# Orders.net
KiCad netlist of a schematic drawn in EAGLE
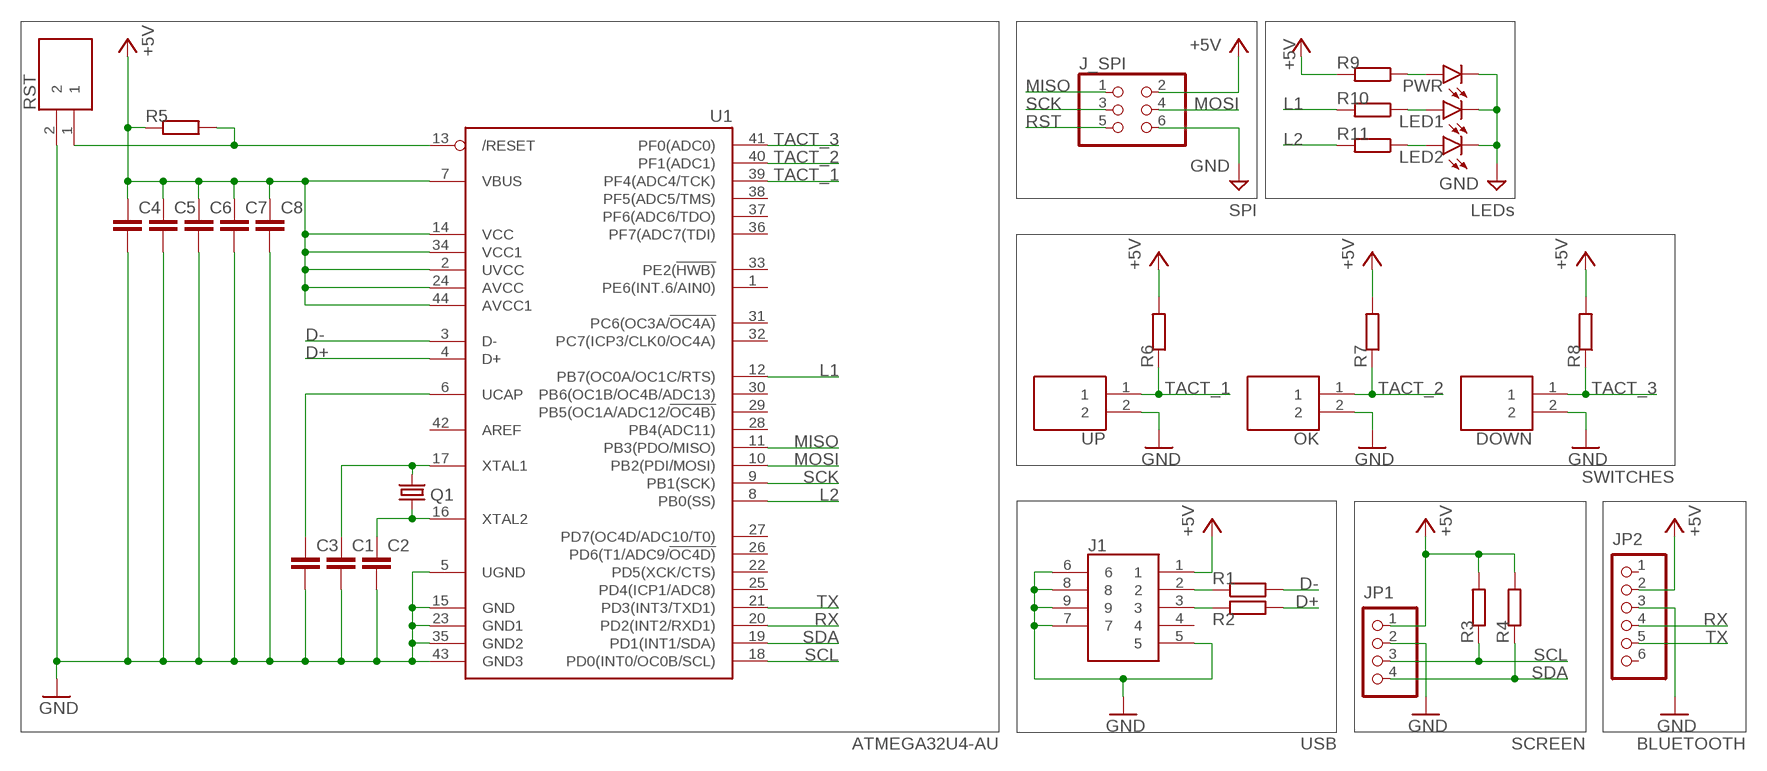
[diagram p0: schematic, sheet 1]

(export (version "E")
  (design (tool "Eeschema 10.0.6"))
  (components
    (comp (ref "C1")
      (value "C-EUC1206")
      (footprint "eagle-import:C1206")
      (libsource (lib "eagle-import") (part "C-EUC1206"))
    )
    (comp (ref "C2")
      (value "C-EUC1206")
      (footprint "eagle-import:C1206")
      (libsource (lib "eagle-import") (part "C-EUC1206"))
    )
    (comp (ref "C3")
      (value "C-EUC1206")
      (footprint "eagle-import:C1206")
      (libsource (lib "eagle-import") (part "C-EUC1206"))
    )
    (comp (ref "C4")
      (value "C-EUC1206")
      (footprint "eagle-import:C1206")
      (libsource (lib "eagle-import") (part "C-EUC1206"))
    )
    (comp (ref "C5")
      (value "C-EUC1206")
      (footprint "eagle-import:C1206")
      (libsource (lib "eagle-import") (part "C-EUC1206"))
    )
    (comp (ref "C6")
      (value "C-EUC1206")
      (footprint "eagle-import:C1206")
      (libsource (lib "eagle-import") (part "C-EUC1206"))
    )
    (comp (ref "C7")
      (value "C-EUC1206")
      (footprint "eagle-import:C1206")
      (libsource (lib "eagle-import") (part "C-EUC1206"))
    )
    (comp (ref "C8")
      (value "C-EUC1206")
      (footprint "eagle-import:C1206")
      (libsource (lib "eagle-import") (part "C-EUC1206"))
    )
    (comp (ref "DOWN")
      (value "KSR231GLFS")
      (footprint "eagle-import:KSR")
      (fields (field (name "MOUSER_PART_NUMBER") "611-KSR231GLFS") (field (name "RS_PART_NUMBER") "7931673P"))
      (libsource (lib "eagle-import") (part "KSR231GLFS"))
    )
    (comp (ref "J1")
      (value "10104111-0001LF")
      (footprint "eagle-import:101041110001LF")
      (fields
        (field (name "MOUSER_PART_NUMBER") "649-10104111-0001LF")
        (field (name "RS_PART_NUMBER") "7142353")
      )
      (libsource (lib "eagle-import") (part "10104111-0001LF"))
    )
    (comp (ref "JP1")
      (value "PINHD-1X4")
      (footprint "eagle-import:1X04")
      (libsource (lib "eagle-import") (part "PINHD-1X4"))
    )
    (comp (ref "JP2")
      (value "PINHD-1X6")
      (footprint "eagle-import:1X06")
      (libsource (lib "eagle-import") (part "PINHD-1X6"))
    )
    (comp (ref "J_SPI")
      (value "PINHD-2X3")
      (footprint "eagle-import:2X03")
      (libsource (lib "eagle-import") (part "PINHD-2X3"))
    )
    (comp (ref "LED1")
      (value "LED3MM")
      (footprint "eagle-import:LED3MM")
      (libsource (lib "eagle-import") (part "LED3MM"))
    )
    (comp (ref "LED2")
      (value "LED3MM")
      (footprint "eagle-import:LED3MM")
      (libsource (lib "eagle-import") (part "LED3MM"))
    )
    (comp (ref "OK")
      (value "KSR231GLFS")
      (footprint "eagle-import:KSR")
      (fields (field (name "MOUSER_PART_NUMBER") "611-KSR231GLFS") (field (name "RS_PART_NUMBER") "7931673P"))
      (libsource (lib "eagle-import") (part "KSR231GLFS"))
    )
    (comp (ref "PWR")
      (value "LED3MM")
      (footprint "eagle-import:LED3MM")
      (libsource (lib "eagle-import") (part "LED3MM"))
    )
    (comp (ref "Q1")
      (value "CRYSTALHC49UP")
      (footprint "eagle-import:HC49UP")
      (libsource (lib "eagle-import") (part "CRYSTALHC49UP"))
    )
    (comp (ref "R1")
      (value "R-EU_R1206")
      (footprint "eagle-import:R1206")
      (libsource (lib "eagle-import") (part "R-EU_R1206"))
    )
    (comp (ref "R2")
      (value "R-EU_R1206")
      (footprint "eagle-import:R1206")
      (libsource (lib "eagle-import") (part "R-EU_R1206"))
    )
    (comp (ref "R3")
      (value "R-EU_R1206")
      (footprint "eagle-import:R1206")
      (libsource (lib "eagle-import") (part "R-EU_R1206"))
    )
    (comp (ref "R4")
      (value "R-EU_R1206")
      (footprint "eagle-import:R1206")
      (libsource (lib "eagle-import") (part "R-EU_R1206"))
    )
    (comp (ref "R5")
      (value "R-EU_R1206")
      (footprint "eagle-import:R1206")
      (libsource (lib "eagle-import") (part "R-EU_R1206"))
    )
    (comp (ref "R6")
      (value "R-EU_R1206")
      (footprint "eagle-import:R1206")
      (libsource (lib "eagle-import") (part "R-EU_R1206"))
    )
    (comp (ref "R7")
      (value "R-EU_R1206")
      (footprint "eagle-import:R1206")
      (libsource (lib "eagle-import") (part "R-EU_R1206"))
    )
    (comp (ref "R8")
      (value "R-EU_R1206")
      (footprint "eagle-import:R1206")
      (libsource (lib "eagle-import") (part "R-EU_R1206"))
    )
    (comp (ref "R9")
      (value "R-EU_R1206")
      (footprint "eagle-import:R1206")
      (libsource (lib "eagle-import") (part "R-EU_R1206"))
    )
    (comp (ref "R10")
      (value "R-EU_R1206")
      (footprint "eagle-import:R1206")
      (libsource (lib "eagle-import") (part "R-EU_R1206"))
    )
    (comp (ref "R11")
      (value "R-EU_R1206")
      (footprint "eagle-import:R1206")
      (libsource (lib "eagle-import") (part "R-EU_R1206"))
    )
    (comp (ref "RST")
      (value "KSR231GLFS")
      (footprint "eagle-import:KSR")
      (fields (field (name "MOUSER_PART_NUMBER") "611-KSR231GLFS") (field (name "RS_PART_NUMBER") "7931673P"))
      (libsource (lib "eagle-import") (part "KSR231GLFS"))
    )
    (comp (ref "U1")
      (value "ATMEGA32U4-AU")
      (footprint "eagle-import:TQFP44")
      (libsource (lib "eagle-import") (part "ATMEGA32U4-AU"))
    )
    (comp (ref "UP")
      (value "KSR231GLFS")
      (footprint "eagle-import:KSR")
      (fields (field (name "MOUSER_PART_NUMBER") "611-KSR231GLFS") (field (name "RS_PART_NUMBER") "7931673P"))
      (libsource (lib "eagle-import") (part "KSR231GLFS"))
    )
  )
  (nets
    (net (code "1") (name "+5V") (class "Default")
      (node (ref "C4") (pin "1") (pinfunction "1_1") (pintype "passive"))
      (node (ref "C5") (pin "1") (pinfunction "1_1") (pintype "passive"))
      (node (ref "C6") (pin "1") (pinfunction "1_1") (pintype "passive"))
      (node (ref "C7") (pin "1") (pinfunction "1_1") (pintype "passive"))
      (node (ref "C8") (pin "1") (pinfunction "1_1") (pintype "passive"))
      (node (ref "J1") (pin "1") (pinfunction "1_1") (pintype "bidirectional"))
      (node (ref "JP1") (pin "1") (pinfunction "1_1") (pintype "passive"))
      (node (ref "JP2") (pin "2") (pinfunction "2_2") (pintype "passive"))
      (node (ref "J_SPI") (pin "2") (pinfunction "2_2") (pintype "passive"))
      (node (ref "R3") (pin "2") (pinfunction "2_2") (pintype "passive"))
      (node (ref "R4") (pin "2") (pinfunction "2_2") (pintype "passive"))
      (node (ref "R5") (pin "1") (pinfunction "1_1") (pintype "passive"))
      (node (ref "R6") (pin "2") (pinfunction "2_2") (pintype "passive"))
      (node (ref "R7") (pin "2") (pinfunction "2_2") (pintype "passive"))
      (node (ref "R8") (pin "2") (pinfunction "2_2") (pintype "passive"))
      (node (ref "R9") (pin "2") (pinfunction "2_2") (pintype "passive"))
      (node (ref "U1") (pin "14") (pinfunction "VCC_14") (pintype "bidirectional"))
      (node (ref "U1") (pin "2") (pinfunction "UVCC_2") (pintype "bidirectional"))
      (node (ref "U1") (pin "24") (pinfunction "AVCC_24") (pintype "bidirectional"))
      (node (ref "U1") (pin "34") (pinfunction "VCC1_34") (pintype "bidirectional"))
      (node (ref "U1") (pin "44") (pinfunction "AVCC1_44") (pintype "bidirectional"))
      (node (ref "U1") (pin "7") (pinfunction "VBUS_7") (pintype "bidirectional"))
    )
    (net (code "2") (name "/D+") (class "Default")
      (node (ref "R2") (pin "2") (pinfunction "2_2") (pintype "passive"))
      (node (ref "U1") (pin "4") (pinfunction "D+_4") (pintype "bidirectional"))
    )
    (net (code "3") (name "/D-") (class "Default")
      (node (ref "R1") (pin "2") (pinfunction "2_2") (pintype "passive"))
      (node (ref "U1") (pin "3") (pinfunction "D-_3") (pintype "bidirectional"))
    )
    (net (code "4") (name "/L1") (class "Default")
      (node (ref "R10") (pin "2") (pinfunction "2_2") (pintype "passive"))
      (node (ref "U1") (pin "12") (pinfunction "PB7(OC0A/OC1C/RTS)_12") (pintype "bidirectional"))
    )
    (net (code "5") (name "/L2") (class "Default")
      (node (ref "R11") (pin "2") (pinfunction "2_2") (pintype "passive"))
      (node (ref "U1") (pin "8") (pinfunction "PB0(SS)_8") (pintype "bidirectional"))
    )
    (net (code "6") (name "/MISO") (class "Default")
      (node (ref "J_SPI") (pin "1") (pinfunction "1_1") (pintype "passive"))
      (node (ref "U1") (pin "11") (pinfunction "PB3(PDO/MISO)_11") (pintype "bidirectional"))
    )
    (net (code "7") (name "/MOSI") (class "Default")
      (node (ref "J_SPI") (pin "4") (pinfunction "4_4") (pintype "passive"))
      (node (ref "U1") (pin "10") (pinfunction "PB2(PDI/MOSI)_10") (pintype "bidirectional"))
    )
    (net (code "8") (name "/RST") (class "Default")
      (node (ref "J_SPI") (pin "5") (pinfunction "5_5") (pintype "passive"))
      (node (ref "R5") (pin "2") (pinfunction "2_2") (pintype "passive"))
      (node (ref "RST") (pin "1") (pinfunction "1_1") (pintype "bidirectional"))
      (node (ref "U1") (pin "13") (pinfunction "/RESET_13") (pintype "bidirectional"))
    )
    (net (code "9") (name "/RX") (class "Default")
      (node (ref "JP2") (pin "4") (pinfunction "4_4") (pintype "passive"))
      (node (ref "U1") (pin "20") (pinfunction "PD2(INT2/RXD1)_20") (pintype "bidirectional"))
    )
    (net (code "10") (name "/SCK") (class "Default")
      (node (ref "J_SPI") (pin "3") (pinfunction "3_3") (pintype "passive"))
      (node (ref "U1") (pin "9") (pinfunction "PB1(SCK)_9") (pintype "bidirectional"))
    )
    (net (code "11") (name "/SCL") (class "Default")
      (node (ref "JP1") (pin "3") (pinfunction "3_3") (pintype "passive"))
      (node (ref "R3") (pin "1") (pinfunction "1_1") (pintype "passive"))
      (node (ref "U1") (pin "18") (pinfunction "PD0(INT0/OC0B/SCL)_18") (pintype "bidirectional"))
    )
    (net (code "12") (name "/SDA") (class "Default")
      (node (ref "JP1") (pin "4") (pinfunction "4_4") (pintype "passive"))
      (node (ref "R4") (pin "1") (pinfunction "1_1") (pintype "passive"))
      (node (ref "U1") (pin "19") (pinfunction "PD1(INT1/SDA)_19") (pintype "bidirectional"))
    )
    (net (code "13") (name "/TACT_1") (class "Default")
      (node (ref "R6") (pin "1") (pinfunction "1_1") (pintype "passive"))
      (node (ref "U1") (pin "39") (pinfunction "PF4(ADC4/TCK)_39") (pintype "bidirectional"))
      (node (ref "UP") (pin "1") (pinfunction "1_1") (pintype "bidirectional"))
    )
    (net (code "14") (name "/TACT_2") (class "Default")
      (node (ref "OK") (pin "1") (pinfunction "1_1") (pintype "bidirectional"))
      (node (ref "R7") (pin "1") (pinfunction "1_1") (pintype "passive"))
      (node (ref "U1") (pin "40") (pinfunction "PF1(ADC1)_40") (pintype "bidirectional"))
    )
    (net (code "15") (name "/TACT_3") (class "Default")
      (node (ref "DOWN") (pin "1") (pinfunction "1_1") (pintype "bidirectional"))
      (node (ref "R8") (pin "1") (pinfunction "1_1") (pintype "passive"))
      (node (ref "U1") (pin "41") (pinfunction "PF0(ADC0)_41") (pintype "bidirectional"))
    )
    (net (code "16") (name "/TX") (class "Default")
      (node (ref "JP2") (pin "5") (pinfunction "5_5") (pintype "passive"))
      (node (ref "U1") (pin "21") (pinfunction "PD3(INT3/TXD1)_21") (pintype "bidirectional"))
    )
    (net (code "17") (name "GND") (class "Default")
      (node (ref "C1") (pin "2") (pinfunction "2_2") (pintype "passive"))
      (node (ref "C2") (pin "2") (pinfunction "2_2") (pintype "passive"))
      (node (ref "C3") (pin "2") (pinfunction "2_2") (pintype "passive"))
      (node (ref "C4") (pin "2") (pinfunction "2_2") (pintype "passive"))
      (node (ref "C5") (pin "2") (pinfunction "2_2") (pintype "passive"))
      (node (ref "C6") (pin "2") (pinfunction "2_2") (pintype "passive"))
      (node (ref "C7") (pin "2") (pinfunction "2_2") (pintype "passive"))
      (node (ref "C8") (pin "2") (pinfunction "2_2") (pintype "passive"))
      (node (ref "DOWN") (pin "2") (pinfunction "2_2") (pintype "bidirectional"))
      (node (ref "J1") (pin "5") (pinfunction "5_5") (pintype "bidirectional"))
      (node (ref "J1") (pin "6") (pinfunction "6_6") (pintype "bidirectional"))
      (node (ref "J1") (pin "7") (pinfunction "7_7") (pintype "bidirectional"))
      (node (ref "J1") (pin "8") (pinfunction "8_8") (pintype "bidirectional"))
      (node (ref "J1") (pin "9") (pinfunction "9_9") (pintype "bidirectional"))
      (node (ref "JP1") (pin "2") (pinfunction "2_2") (pintype "passive"))
      (node (ref "JP2") (pin "3") (pinfunction "3_3") (pintype "passive"))
      (node (ref "J_SPI") (pin "6") (pinfunction "6_6") (pintype "passive"))
      (node (ref "LED1") (pin "K") (pinfunction "C_K") (pintype "passive"))
      (node (ref "LED2") (pin "K") (pinfunction "C_K") (pintype "passive"))
      (node (ref "OK") (pin "2") (pinfunction "2_2") (pintype "bidirectional"))
      (node (ref "PWR") (pin "K") (pinfunction "C_K") (pintype "passive"))
      (node (ref "RST") (pin "2") (pinfunction "2_2") (pintype "bidirectional"))
      (node (ref "U1") (pin "15") (pinfunction "GND_15") (pintype "bidirectional"))
      (node (ref "U1") (pin "23") (pinfunction "GND1_23") (pintype "bidirectional"))
      (node (ref "U1") (pin "35") (pinfunction "GND2_35") (pintype "bidirectional"))
      (node (ref "U1") (pin "43") (pinfunction "GND3_43") (pintype "bidirectional"))
      (node (ref "U1") (pin "5") (pinfunction "UGND_5") (pintype "bidirectional"))
      (node (ref "UP") (pin "2") (pinfunction "2_2") (pintype "bidirectional"))
    )
    (net (code "18") (name "Net-(J1-Pad2)") (class "Default")
      (node (ref "J1") (pin "2") (pinfunction "2_2") (pintype "bidirectional"))
      (node (ref "R1") (pin "1") (pinfunction "1_1") (pintype "passive"))
    )
    (net (code "19") (name "Net-(J1-Pad3)") (class "Default")
      (node (ref "J1") (pin "3") (pinfunction "3_3") (pintype "bidirectional"))
      (node (ref "R2") (pin "1") (pinfunction "1_1") (pintype "passive"))
    )
    (net (code "20") (name "Net-(LED1-PadA)") (class "Default")
      (node (ref "LED1") (pin "A") (pinfunction "A_A") (pintype "passive"))
      (node (ref "R10") (pin "1") (pinfunction "1_1") (pintype "passive"))
    )
    (net (code "21") (name "Net-(LED2-PadA)") (class "Default")
      (node (ref "LED2") (pin "A") (pinfunction "A_A") (pintype "passive"))
      (node (ref "R11") (pin "1") (pinfunction "1_1") (pintype "passive"))
    )
    (net (code "22") (name "Net-(PWR-PadA)") (class "Default")
      (node (ref "PWR") (pin "A") (pinfunction "A_A") (pintype "passive"))
      (node (ref "R9") (pin "1") (pinfunction "1_1") (pintype "passive"))
    )
    (net (code "23") (name "Net-(U1-UCAP)") (class "Default")
      (node (ref "C3") (pin "1") (pinfunction "1_1") (pintype "passive"))
      (node (ref "U1") (pin "6") (pinfunction "UCAP_6") (pintype "bidirectional"))
    )
    (net (code "24") (name "Net-(U1-XTAL1)") (class "Default")
      (node (ref "C1") (pin "1") (pinfunction "1_1") (pintype "passive"))
      (node (ref "Q1") (pin "2") (pinfunction "2_2") (pintype "passive"))
      (node (ref "U1") (pin "17") (pinfunction "XTAL1_17") (pintype "bidirectional"))
    )
    (net (code "25") (name "Net-(U1-XTAL2)") (class "Default")
      (node (ref "C2") (pin "1") (pinfunction "1_1") (pintype "passive"))
      (node (ref "Q1") (pin "1") (pinfunction "1_1") (pintype "passive"))
      (node (ref "U1") (pin "16") (pinfunction "XTAL2_16") (pintype "bidirectional"))
    )
    (net (code "26") (name "unconnected-(J1-Pad4)") (class "Default")
      (node (ref "J1") (pin "4") (pinfunction "4_4") (pintype "bidirectional"))
    )
    (net (code "27") (name "unconnected-(JP2-Pad1)") (class "Default")
      (node (ref "JP2") (pin "1") (pinfunction "1_1") (pintype "passive"))
    )
    (net (code "28") (name "unconnected-(JP2-Pad6)") (class "Default")
      (node (ref "JP2") (pin "6") (pinfunction "6_6") (pintype "passive"))
    )
    (net (code "29") (name "unconnected-(U1-AREF-Pad42)") (class "Default")
      (node (ref "U1") (pin "42") (pinfunction "AREF_42") (pintype "bidirectional"))
    )
    (net (code "30") (name "unconnected-(U1-PB4(ADC11)-Pad28)") (class "Default")
      (node (ref "U1") (pin "28") (pinfunction "PB4(ADC11)_28") (pintype "bidirectional"))
    )
    (net (code "31") (name "unconnected-(U1-PB5(OC1A{slash}ADC12{slash}~{OC4B})-Pad29)") (class "Default")
      (node (ref "U1") (pin "29") (pinfunction "PB5(OC1A/ADC12/~{OC4B})_29") (pintype "bidirectional"))
    )
    (net (code "32") (name "unconnected-(U1-PB6(OC1B{slash}OC4B{slash}ADC13)-Pad30)") (class "Default")
      (node (ref "U1") (pin "30") (pinfunction "PB6(OC1B/OC4B/ADC13)_30") (pintype "bidirectional"))
    )
    (net (code "33") (name "unconnected-(U1-PC6(OC3A{slash}~{OC4A})-Pad31)") (class "Default")
      (node (ref "U1") (pin "31") (pinfunction "PC6(OC3A/~{OC4A})_31") (pintype "bidirectional"))
    )
    (net (code "34") (name "unconnected-(U1-PC7(ICP3{slash}CLK0{slash}OC4A)-Pad32)") (class "Default")
      (node (ref "U1") (pin "32") (pinfunction "PC7(ICP3/CLK0/OC4A)_32") (pintype "bidirectional"))
    )
    (net (code "35") (name "unconnected-(U1-PD4(ICP1{slash}ADC8)-Pad25)") (class "Default")
      (node (ref "U1") (pin "25") (pinfunction "PD4(ICP1/ADC8)_25") (pintype "bidirectional"))
    )
    (net (code "36") (name "unconnected-(U1-PD5(XCK{slash}CTS)-Pad22)") (class "Default")
      (node (ref "U1") (pin "22") (pinfunction "PD5(XCK/CTS)_22") (pintype "bidirectional"))
    )
    (net (code "37") (name "unconnected-(U1-PD6(T1{slash}ADC9{slash}~{OC4D})-Pad26)") (class "Default")
      (node (ref "U1") (pin "26") (pinfunction "PD6(T1/ADC9/~{OC4D})_26") (pintype "bidirectional"))
    )
    (net (code "38") (name "unconnected-(U1-PD7(OC4D{slash}ADC10{slash}T0)-Pad27)") (class "Default")
      (node (ref "U1") (pin "27") (pinfunction "PD7(OC4D/ADC10/T0)_27") (pintype "bidirectional"))
    )
    (net (code "39") (name "unconnected-(U1-PE2(~{HWB})-Pad33)") (class "Default")
      (node (ref "U1") (pin "33") (pinfunction "PE2(~{HWB})_33") (pintype "bidirectional"))
    )
    (net (code "40") (name "unconnected-(U1-PE6(INT.6{slash}AIN0)-Pad1)") (class "Default")
      (node (ref "U1") (pin "1") (pinfunction "PE6(INT.6/AIN0)_1") (pintype "bidirectional"))
    )
    (net (code "41") (name "unconnected-(U1-PF5(ADC5{slash}TMS)-Pad38)") (class "Default")
      (node (ref "U1") (pin "38") (pinfunction "PF5(ADC5/TMS)_38") (pintype "bidirectional"))
    )
    (net (code "42") (name "unconnected-(U1-PF6(ADC6{slash}TDO)-Pad37)") (class "Default")
      (node (ref "U1") (pin "37") (pinfunction "PF6(ADC6/TDO)_37") (pintype "bidirectional"))
    )
    (net (code "43") (name "unconnected-(U1-PF7(ADC7(TDI)-Pad36)") (class "Default")
      (node (ref "U1") (pin "36") (pinfunction "PF7(ADC7(TDI)_36") (pintype "bidirectional"))
    )
  )
)
